# Game_of_Life_v2.net
KiCad netlist of a schematic drawn in EAGLE
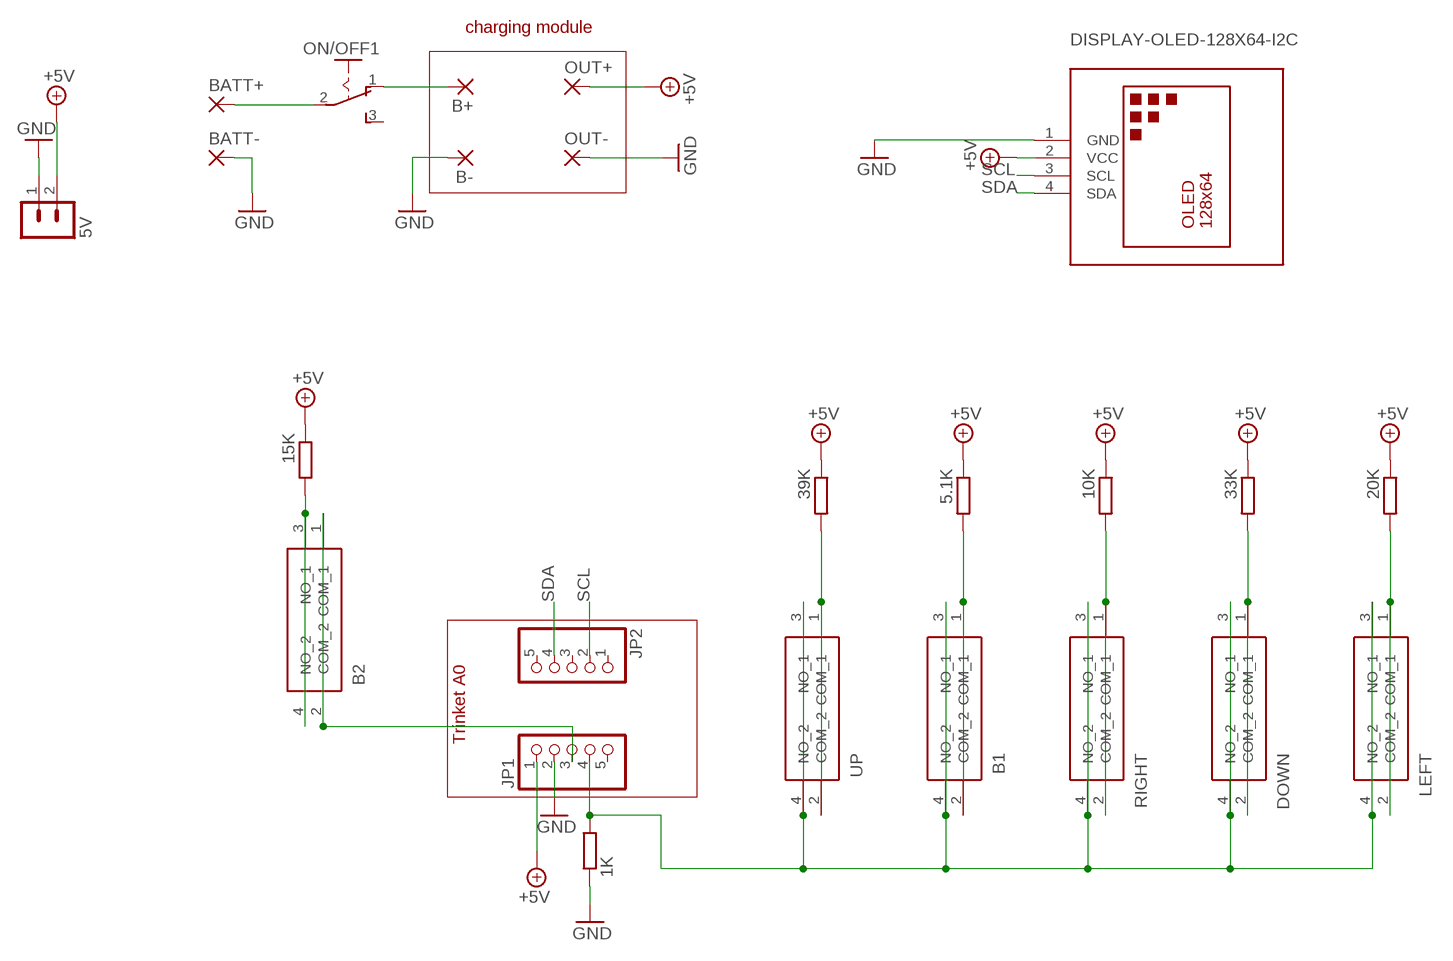
[diagram p0: schematic, sheet 1]

(export (version "E")
  (design (tool "Eeschema 10.0.6"))
  (components
    (comp (ref "5V")
      (value "B2B-PH-K-S")
      (footprint "eagle-import:B2B-PH-K-S")
      (libsource (lib "eagle-import") (part "B2B-PH-K-S"))
    )
    (comp (ref "B+")
      (value "SMD5")
      (footprint "eagle-import:SMD2,54-5,08")
      (libsource (lib "eagle-import") (part "SMD5"))
    )
    (comp (ref "B-")
      (value "SMD5")
      (footprint "eagle-import:SMD2,54-5,08")
      (libsource (lib "eagle-import") (part "SMD5"))
    )
    (comp (ref "B1")
      (value "101-0364-EV")
      (footprint "eagle-import:1010364EV")
      (libsource (lib "eagle-import") (part "101-0364-EV"))
    )
    (comp (ref "B2")
      (value "101-0364-EV")
      (footprint "eagle-import:1010364EV")
      (libsource (lib "eagle-import") (part "101-0364-EV"))
    )
    (comp (ref "BATT+")
      (value "SMD5")
      (footprint "eagle-import:SMD2,54-5,08")
      (libsource (lib "eagle-import") (part "SMD5"))
    )
    (comp (ref "BATT-")
      (value "SMD5")
      (footprint "eagle-import:SMD2,54-5,08")
      (libsource (lib "eagle-import") (part "SMD5"))
    )
    (comp (ref "DOWN")
      (value "101-0364-EV")
      (footprint "eagle-import:1010364EV")
      (libsource (lib "eagle-import") (part "101-0364-EV"))
    )
    (comp (ref "JP1")
      (value "PINHD-1X5")
      (footprint "eagle-import:1X05")
      (libsource (lib "eagle-import") (part "PINHD-1X5"))
    )
    (comp (ref "JP2")
      (value "PINHD-1X5")
      (footprint "eagle-import:1X05")
      (libsource (lib "eagle-import") (part "PINHD-1X5"))
    )
    (comp (ref "LEFT")
      (value "101-0364-EV")
      (footprint "eagle-import:1010364EV")
      (libsource (lib "eagle-import") (part "101-0364-EV"))
    )
    (comp (ref "ON/OFF1")
      (value "M251")
      (footprint "eagle-import:M251")
      (libsource (lib "eagle-import") (part "M251"))
    )
    (comp (ref "OUT+")
      (value "SMD5")
      (footprint "eagle-import:SMD2,54-5,08")
      (libsource (lib "eagle-import") (part "SMD5"))
    )
    (comp (ref "OUT-")
      (value "SMD5")
      (footprint "eagle-import:SMD2,54-5,08")
      (libsource (lib "eagle-import") (part "SMD5"))
    )
    (comp (ref "R1")
      (value "1K")
      (footprint "eagle-import:0207_10")
      (libsource (lib "eagle-import") (part "R-EU_0207/10"))
    )
    (comp (ref "R2")
      (value "20K")
      (footprint "eagle-import:0207_10")
      (libsource (lib "eagle-import") (part "R-EU_0207/10"))
    )
    (comp (ref "R3")
      (value "39K")
      (footprint "eagle-import:0207_10")
      (libsource (lib "eagle-import") (part "R-EU_0207/10"))
    )
    (comp (ref "R4")
      (value "10K")
      (footprint "eagle-import:0207_10")
      (libsource (lib "eagle-import") (part "R-EU_0207/10"))
    )
    (comp (ref "R5")
      (value "33K")
      (footprint "eagle-import:0207_10")
      (libsource (lib "eagle-import") (part "R-EU_0207/10"))
    )
    (comp (ref "R6")
      (value "5.1K")
      (footprint "eagle-import:0207_10")
      (libsource (lib "eagle-import") (part "R-EU_0207/10"))
    )
    (comp (ref "R7")
      (value "15K")
      (footprint "eagle-import:0207_10")
      (libsource (lib "eagle-import") (part "R-EU_0207/10"))
    )
    (comp (ref "RIGHT")
      (value "101-0364-EV")
      (footprint "eagle-import:1010364EV")
      (libsource (lib "eagle-import") (part "101-0364-EV"))
    )
    (comp (ref "U$2")
      (value "DISPLAY-OLED-128X64-I2C")
      (footprint "eagle-import:DISPLAY-OLED-128X64-I2C")
      (libsource (lib "eagle-import") (part "DISPLAY-OLED-128X64-I2C"))
    )
    (comp (ref "UP")
      (value "101-0364-EV")
      (footprint "eagle-import:1010364EV")
      (libsource (lib "eagle-import") (part "101-0364-EV"))
    )
  )
  (nets
    (net (code "1") (name "+5V") (class "Default")
      (node (ref "5V") (pin "2") (pinfunction "2_2") (pintype "passive"))
      (node (ref "JP1") (pin "1") (pinfunction "1_1") (pintype "passive"))
      (node (ref "OUT+") (pin "1") (pinfunction "P_1") (pintype "passive"))
      (node (ref "R2") (pin "1") (pinfunction "1_1") (pintype "passive"))
      (node (ref "R3") (pin "1") (pinfunction "1_1") (pintype "passive"))
      (node (ref "R4") (pin "1") (pinfunction "1_1") (pintype "passive"))
      (node (ref "R5") (pin "1") (pinfunction "1_1") (pintype "passive"))
      (node (ref "R6") (pin "1") (pinfunction "1_1") (pintype "passive"))
      (node (ref "R7") (pin "1") (pinfunction "1_1") (pintype "passive"))
      (node (ref "U$2") (pin "2") (pinfunction "VCC_2") (pintype "power_in"))
    )
    (net (code "2") (name "/SCL") (class "Default")
      (node (ref "JP2") (pin "2") (pinfunction "2_2") (pintype "passive"))
      (node (ref "U$2") (pin "3") (pinfunction "SCL_3") (pintype "bidirectional"))
    )
    (net (code "3") (name "/SDA") (class "Default")
      (node (ref "JP2") (pin "4") (pinfunction "4_4") (pintype "passive"))
      (node (ref "U$2") (pin "4") (pinfunction "SDA_4") (pintype "bidirectional"))
    )
    (net (code "4") (name "GND") (class "Default")
      (node (ref "5V") (pin "1") (pinfunction "1_1") (pintype "passive"))
      (node (ref "B-") (pin "1") (pinfunction "P_1") (pintype "passive"))
      (node (ref "BATT-") (pin "1") (pinfunction "P_1") (pintype "passive"))
      (node (ref "JP1") (pin "2") (pinfunction "2_2") (pintype "passive"))
      (node (ref "OUT-") (pin "1") (pinfunction "P_1") (pintype "passive"))
      (node (ref "R1") (pin "1") (pinfunction "1_1") (pintype "passive"))
      (node (ref "U$2") (pin "1") (pinfunction "GND_1") (pintype "power_in"))
    )
    (net (code "5") (name "Net-(B+-P)") (class "Default")
      (node (ref "B+") (pin "1") (pinfunction "P_1") (pintype "passive"))
      (node (ref "ON/OFF1") (pin "1") (pinfunction "O_1") (pintype "passive"))
    )
    (net (code "6") (name "Net-(B1-COM_1)") (class "Default")
      (node (ref "B1") (pin "1") (pinfunction "COM_1_1") (pintype "bidirectional"))
      (node (ref "B1") (pin "2") (pinfunction "COM_2_2") (pintype "bidirectional"))
      (node (ref "R6") (pin "2") (pinfunction "2_2") (pintype "passive"))
    )
    (net (code "7") (name "Net-(B1-NO_1)") (class "Default")
      (node (ref "B1") (pin "3") (pinfunction "NO_1_3") (pintype "bidirectional"))
      (node (ref "B1") (pin "4") (pinfunction "NO_2_4") (pintype "bidirectional"))
      (node (ref "DOWN") (pin "3") (pinfunction "NO_1_3") (pintype "bidirectional"))
      (node (ref "DOWN") (pin "4") (pinfunction "NO_2_4") (pintype "bidirectional"))
      (node (ref "JP1") (pin "4") (pinfunction "4_4") (pintype "passive"))
      (node (ref "LEFT") (pin "3") (pinfunction "NO_1_3") (pintype "bidirectional"))
      (node (ref "LEFT") (pin "4") (pinfunction "NO_2_4") (pintype "bidirectional"))
      (node (ref "R1") (pin "2") (pinfunction "2_2") (pintype "passive"))
      (node (ref "RIGHT") (pin "3") (pinfunction "NO_1_3") (pintype "bidirectional"))
      (node (ref "RIGHT") (pin "4") (pinfunction "NO_2_4") (pintype "bidirectional"))
      (node (ref "UP") (pin "3") (pinfunction "NO_1_3") (pintype "bidirectional"))
      (node (ref "UP") (pin "4") (pinfunction "NO_2_4") (pintype "bidirectional"))
    )
    (net (code "8") (name "Net-(B2-COM_1)") (class "Default")
      (node (ref "B2") (pin "1") (pinfunction "COM_1_1") (pintype "bidirectional"))
      (node (ref "B2") (pin "2") (pinfunction "COM_2_2") (pintype "bidirectional"))
      (node (ref "JP1") (pin "3") (pinfunction "3_3") (pintype "passive"))
    )
    (net (code "9") (name "Net-(B2-NO_1)") (class "Default")
      (node (ref "B2") (pin "3") (pinfunction "NO_1_3") (pintype "bidirectional"))
      (node (ref "B2") (pin "4") (pinfunction "NO_2_4") (pintype "bidirectional"))
      (node (ref "R7") (pin "2") (pinfunction "2_2") (pintype "passive"))
    )
    (net (code "10") (name "Net-(BATT+-P)") (class "Default")
      (node (ref "BATT+") (pin "1") (pinfunction "P_1") (pintype "passive"))
      (node (ref "ON/OFF1") (pin "2") (pinfunction "P_2") (pintype "passive"))
    )
    (net (code "11") (name "Net-(DOWN-COM_1)") (class "Default")
      (node (ref "DOWN") (pin "1") (pinfunction "COM_1_1") (pintype "bidirectional"))
      (node (ref "DOWN") (pin "2") (pinfunction "COM_2_2") (pintype "bidirectional"))
      (node (ref "R5") (pin "2") (pinfunction "2_2") (pintype "passive"))
    )
    (net (code "12") (name "Net-(LEFT-COM_1)") (class "Default")
      (node (ref "LEFT") (pin "1") (pinfunction "COM_1_1") (pintype "bidirectional"))
      (node (ref "LEFT") (pin "2") (pinfunction "COM_2_2") (pintype "bidirectional"))
      (node (ref "R2") (pin "2") (pinfunction "2_2") (pintype "passive"))
    )
    (net (code "13") (name "Net-(RIGHT-COM_1)") (class "Default")
      (node (ref "R4") (pin "2") (pinfunction "2_2") (pintype "passive"))
      (node (ref "RIGHT") (pin "1") (pinfunction "COM_1_1") (pintype "bidirectional"))
      (node (ref "RIGHT") (pin "2") (pinfunction "COM_2_2") (pintype "bidirectional"))
    )
    (net (code "14") (name "Net-(UP-COM_1)") (class "Default")
      (node (ref "R3") (pin "2") (pinfunction "2_2") (pintype "passive"))
      (node (ref "UP") (pin "1") (pinfunction "COM_1_1") (pintype "bidirectional"))
      (node (ref "UP") (pin "2") (pinfunction "COM_2_2") (pintype "bidirectional"))
    )
    (net (code "15") (name "unconnected-(JP1-Pad5)") (class "Default")
      (node (ref "JP1") (pin "5") (pinfunction "5_5") (pintype "passive"))
    )
    (net (code "16") (name "unconnected-(JP2-Pad1)") (class "Default")
      (node (ref "JP2") (pin "1") (pinfunction "1_1") (pintype "passive"))
    )
    (net (code "17") (name "unconnected-(JP2-Pad3)") (class "Default")
      (node (ref "JP2") (pin "3") (pinfunction "3_3") (pintype "passive"))
    )
    (net (code "18") (name "unconnected-(JP2-Pad5)") (class "Default")
      (node (ref "JP2") (pin "5") (pinfunction "5_5") (pintype "passive"))
    )
    (net (code "19") (name "unconnected-(ON/OFF1-S-Pad3)") (class "Default")
      (node (ref "ON/OFF1") (pin "3") (pinfunction "S_3") (pintype "passive"))
    )
  )
)
